# Block_Diagram.net
KiCad netlist of a schematic drawn in Altium Designer
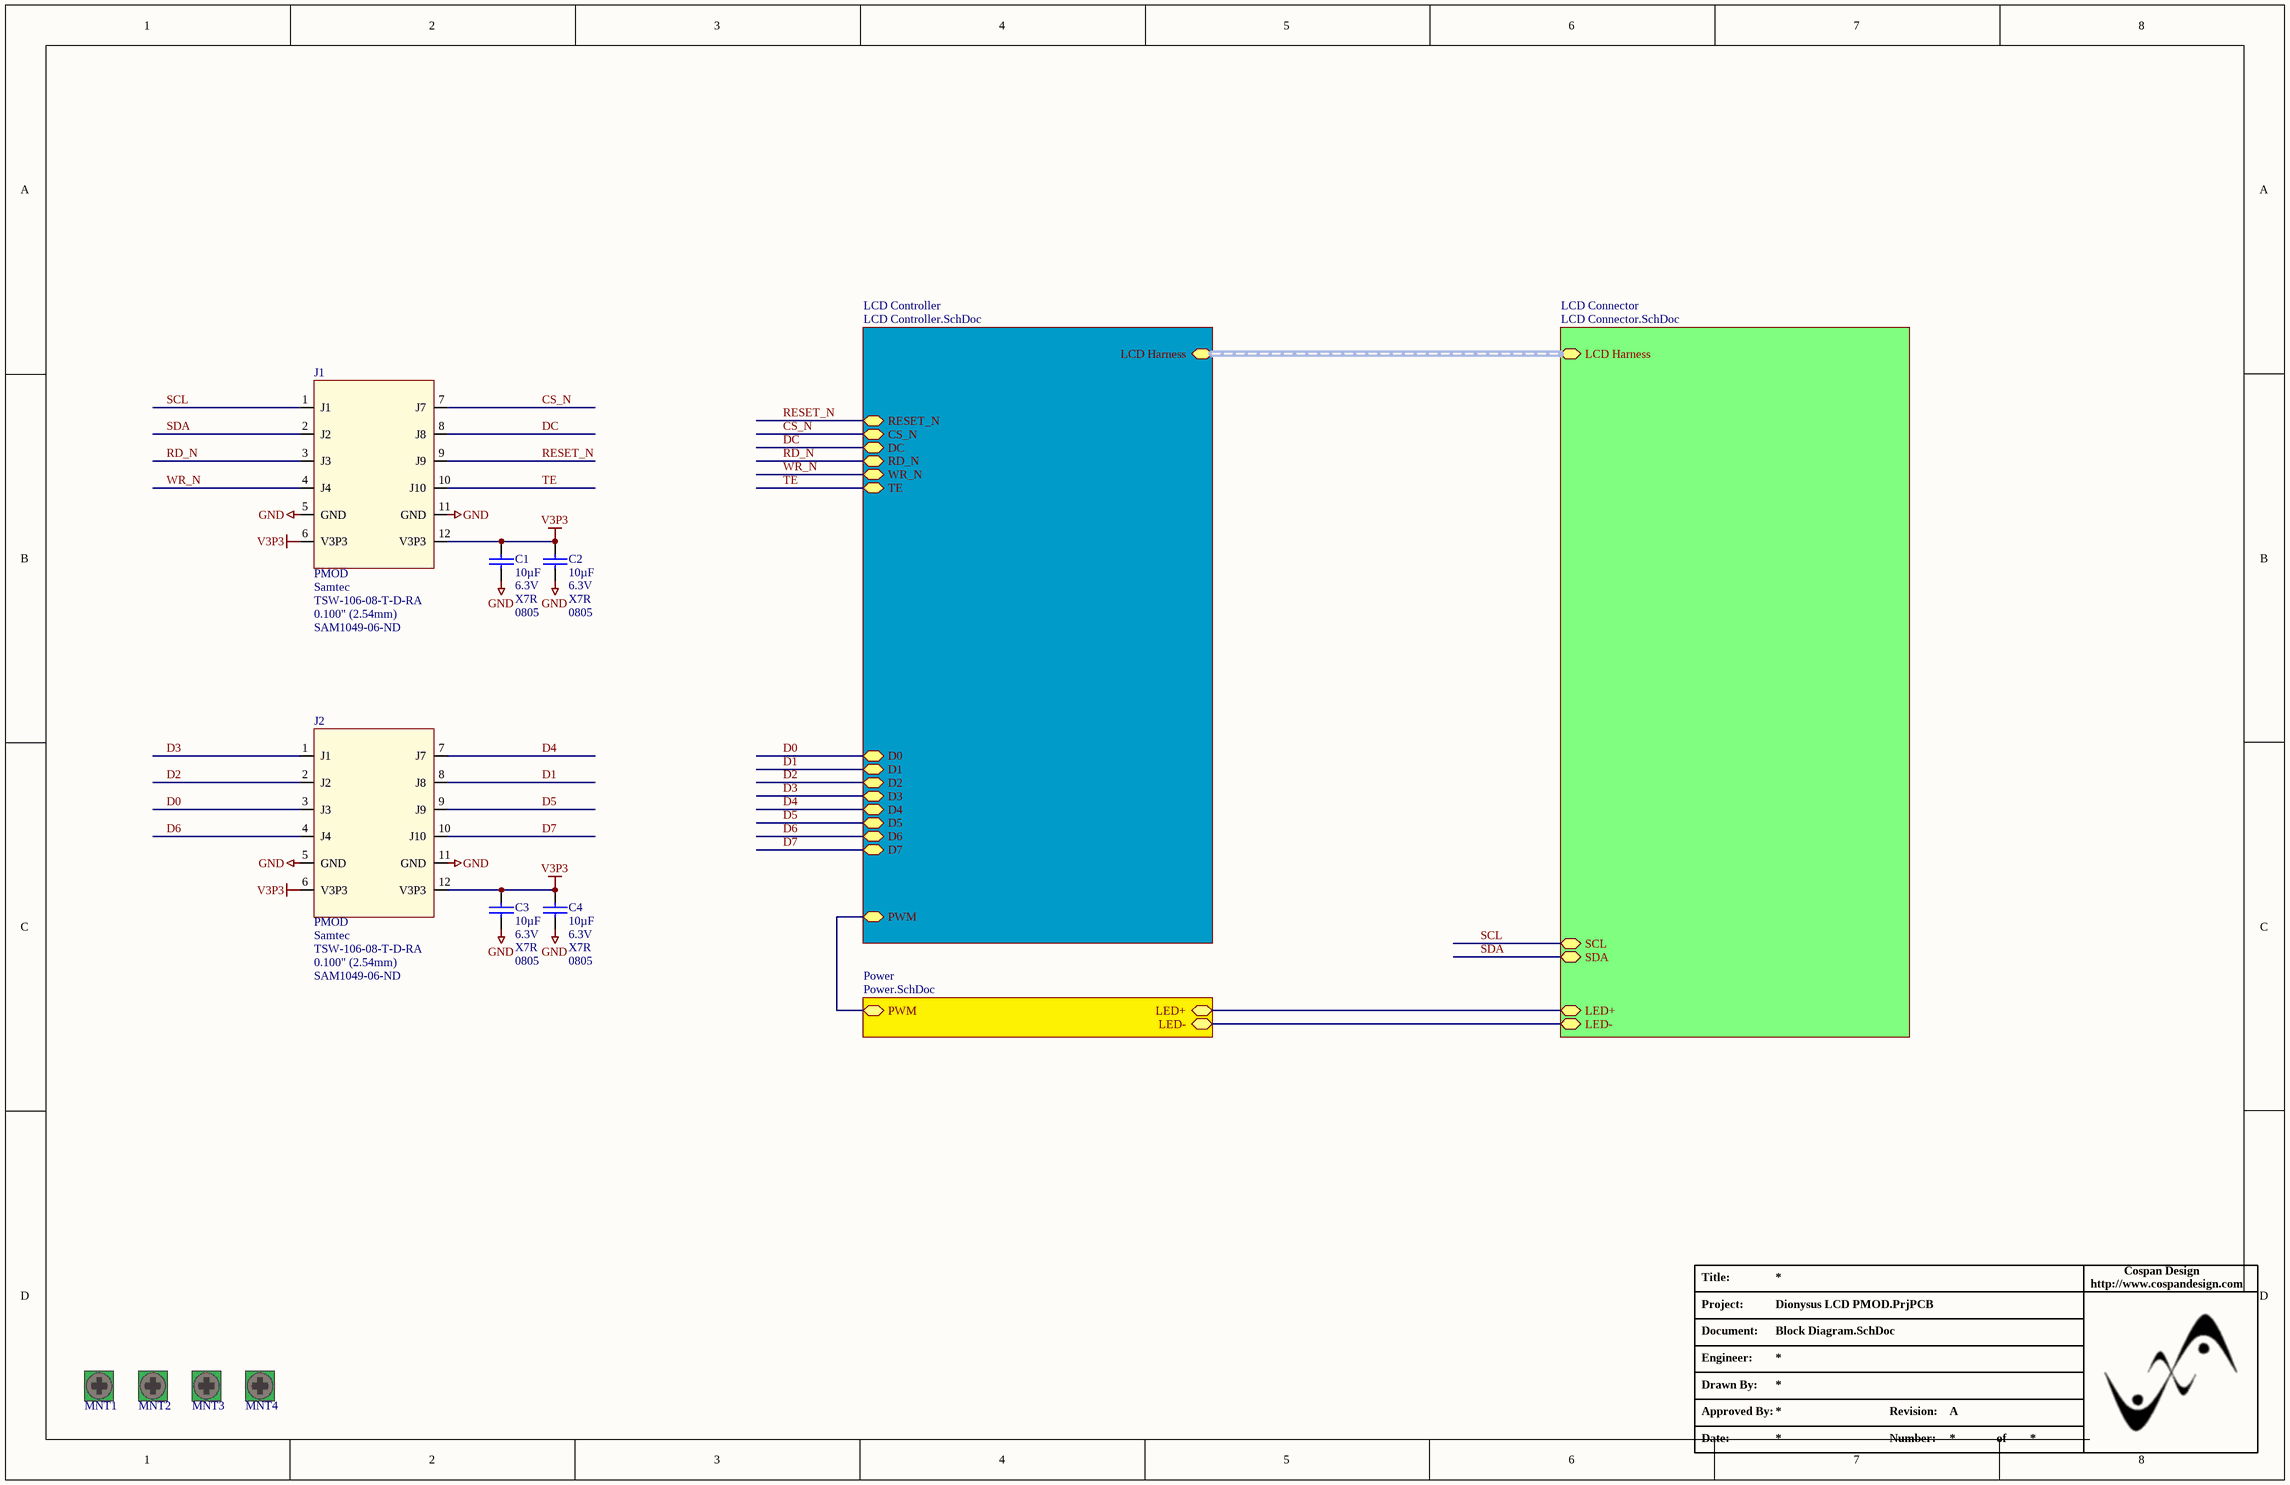
[diagram p0: Block Diagram.SchDoc]

(export (version "E")
  (design (tool "Eeschema 10.0.6"))
  (components
    (comp (ref "C1")
      (value "10uF")
      (footprint "C_ERA-0805")
      (description "CAP CER 10UF 6.3V X7R 10% 0805")
      (fields
        (field (name "MANUFACTURER") "Taiyo Yuden")
        (field (name "MANUFACTURER PART NUMBER") "JMK212BJ106KD-T")
        (field (name "CAPACITANCE") "10µF")
        (field (name "VOLTAGE - RATED") "6.3V")
        (field (name "TEMPERATURE COEFFICIENT") "X7R")
        (field (name "PACKAGE / CASE") "0805")
      )
      (libsource (lib "Main Library") (part "C_0805_10UF_6.3V"))
    )
    (comp (ref "C2")
      (value "10uF")
      (footprint "C_ERA-0805")
      (description "CAP CER 10UF 6.3V X7R 10% 0805")
      (fields
        (field (name "MANUFACTURER") "Taiyo Yuden")
        (field (name "MANUFACTURER PART NUMBER") "JMK212BJ106KD-T")
        (field (name "CAPACITANCE") "10µF")
        (field (name "VOLTAGE - RATED") "6.3V")
        (field (name "TEMPERATURE COEFFICIENT") "X7R")
        (field (name "PACKAGE / CASE") "0805")
      )
      (libsource (lib "Main Library") (part "C_0805_10UF_6.3V"))
    )
    (comp (ref "C3")
      (value "10uF")
      (footprint "C_ERA-0805")
      (description "CAP CER 10UF 6.3V X7R 10% 0805")
      (fields
        (field (name "MANUFACTURER") "Taiyo Yuden")
        (field (name "MANUFACTURER PART NUMBER") "JMK212BJ106KD-T")
        (field (name "CAPACITANCE") "10µF")
        (field (name "VOLTAGE - RATED") "6.3V")
        (field (name "TEMPERATURE COEFFICIENT") "X7R")
        (field (name "PACKAGE / CASE") "0805")
      )
      (libsource (lib "Main Library") (part "C_0805_10UF_6.3V"))
    )
    (comp (ref "C4")
      (value "10uF")
      (footprint "C_ERA-0805")
      (description "CAP CER 10UF 6.3V X7R 10% 0805")
      (fields
        (field (name "MANUFACTURER") "Taiyo Yuden")
        (field (name "MANUFACTURER PART NUMBER") "JMK212BJ106KD-T")
        (field (name "CAPACITANCE") "10µF")
        (field (name "VOLTAGE - RATED") "6.3V")
        (field (name "TEMPERATURE COEFFICIENT") "X7R")
        (field (name "PACKAGE / CASE") "0805")
      )
      (libsource (lib "Main Library") (part "C_0805_10UF_6.3V"))
    )
    (comp (ref "J1")
      (value "PMOD")
      (footprint "PMOD PERIPHERAL")
      (description "CONN HEADER 12PS .100 DL R/A TIN")
      (fields
        (field (name "MANUFACTURER") "Samtec")
        (field (name "MANUFACTURER PART NUMBER") "TSW-106-08-T-D-RA")
        (field (name "PITCH") "0.100\" (2.54mm)")
        (field (name "SUPPLIER PART NUMBER 1") "SAM1049-06-ND")
      )
      (libsource (lib "Main Library") (part "J_PMOD_PERIPH"))
    )
    (comp (ref "J2")
      (value "PMOD")
      (footprint "PMOD PERIPHERAL")
      (description "CONN HEADER 12PS .100 DL R/A TIN")
      (fields
        (field (name "MANUFACTURER") "Samtec")
        (field (name "MANUFACTURER PART NUMBER") "TSW-106-08-T-D-RA")
        (field (name "PITCH") "0.100\" (2.54mm)")
        (field (name "SUPPLIER PART NUMBER 1") "SAM1049-06-ND")
      )
      (libsource (lib "Main Library") (part "J_PMOD_PERIPH"))
    )
    (comp (ref "MNT1")
      (value "Mounting Hole")
      (footprint "MNT_4-40")
      (libsource (lib "Main Library") (part "MNT_440_HOLE"))
    )
    (comp (ref "MNT2")
      (value "Mounting Hole")
      (footprint "MNT_4-40")
      (libsource (lib "Main Library") (part "MNT_440_HOLE"))
    )
    (comp (ref "MNT3")
      (value "Mounting Hole")
      (footprint "MNT_4-40")
      (libsource (lib "Main Library") (part "MNT_440_HOLE"))
    )
    (comp (ref "MNT4")
      (value "Mounting Hole")
      (footprint "MNT_4-40")
      (libsource (lib "Main Library") (part "MNT_440_HOLE"))
    )
  )
  (nets
    (net (code "1") (name "/CS_N") (class "Default")
      (node (ref "J1") (pin "7") (pinfunction "J7_7") (pintype "passive"))
    )
    (net (code "2") (name "/D0") (class "Default")
      (node (ref "J2") (pin "3") (pinfunction "J3_3") (pintype "passive"))
    )
    (net (code "3") (name "/D1") (class "Default")
      (node (ref "J2") (pin "8") (pinfunction "J8_8") (pintype "passive"))
    )
    (net (code "4") (name "/D2") (class "Default")
      (node (ref "J2") (pin "2") (pinfunction "J2_2") (pintype "passive"))
    )
    (net (code "5") (name "/D3") (class "Default")
      (node (ref "J2") (pin "1") (pinfunction "J1_1") (pintype "passive"))
    )
    (net (code "6") (name "/D4") (class "Default")
      (node (ref "J2") (pin "7") (pinfunction "J7_7") (pintype "passive"))
    )
    (net (code "7") (name "/D5") (class "Default")
      (node (ref "J2") (pin "9") (pinfunction "J9_9") (pintype "passive"))
    )
    (net (code "8") (name "/D6") (class "Default")
      (node (ref "J2") (pin "4") (pinfunction "J4_4") (pintype "passive"))
    )
    (net (code "9") (name "/D7") (class "Default")
      (node (ref "J2") (pin "10") (pinfunction "J10_10") (pintype "passive"))
    )
    (net (code "10") (name "/DC") (class "Default")
      (node (ref "J1") (pin "8") (pinfunction "J8_8") (pintype "passive"))
    )
    (net (code "15") (name "/RD_N") (class "Default")
      (node (ref "J1") (pin "3") (pinfunction "J3_3") (pintype "passive"))
    )
    (net (code "16") (name "/RESET_N") (class "Default")
      (node (ref "J1") (pin "9") (pinfunction "J9_9") (pintype "passive"))
    )
    (net (code "17") (name "/SCL") (class "Default")
      (node (ref "J1") (pin "1") (pinfunction "J1_1") (pintype "passive"))
    )
    (net (code "18") (name "/SDA") (class "Default")
      (node (ref "J1") (pin "2") (pinfunction "J2_2") (pintype "passive"))
    )
    (net (code "19") (name "/TE") (class "Default")
      (node (ref "J1") (pin "10") (pinfunction "J10_10") (pintype "passive"))
    )
    (net (code "20") (name "/WR_N") (class "Default")
      (node (ref "J1") (pin "4") (pinfunction "J4_4") (pintype "passive"))
    )
    (net (code "21") (name "GND") (class "Default")
      (node (ref "C1") (pin "1") (pinfunction "1_1") (pintype "passive"))
      (node (ref "C2") (pin "1") (pinfunction "1_1") (pintype "passive"))
      (node (ref "C3") (pin "1") (pinfunction "1_1") (pintype "passive"))
      (node (ref "C4") (pin "1") (pinfunction "1_1") (pintype "passive"))
      (node (ref "J1") (pin "11") (pinfunction "GND_11") (pintype "passive"))
      (node (ref "J1") (pin "5") (pinfunction "GND_5") (pintype "passive"))
      (node (ref "J2") (pin "11") (pinfunction "GND_11") (pintype "passive"))
      (node (ref "J2") (pin "5") (pinfunction "GND_5") (pintype "passive"))
    )
    (net (code "22") (name "V3P3") (class "Default")
      (node (ref "C1") (pin "2") (pinfunction "2_2") (pintype "passive"))
      (node (ref "C2") (pin "2") (pinfunction "2_2") (pintype "passive"))
      (node (ref "C3") (pin "2") (pinfunction "2_2") (pintype "passive"))
      (node (ref "C4") (pin "2") (pinfunction "2_2") (pintype "passive"))
      (node (ref "J1") (pin "12") (pinfunction "V3P3_12") (pintype "passive"))
      (node (ref "J1") (pin "6") (pinfunction "V3P3_6") (pintype "passive"))
      (node (ref "J2") (pin "12") (pinfunction "V3P3_12") (pintype "passive"))
      (node (ref "J2") (pin "6") (pinfunction "V3P3_6") (pintype "passive"))
    )
  )
)
